# Sheet2.net
KiCad netlist of a schematic drawn in Altium Designer
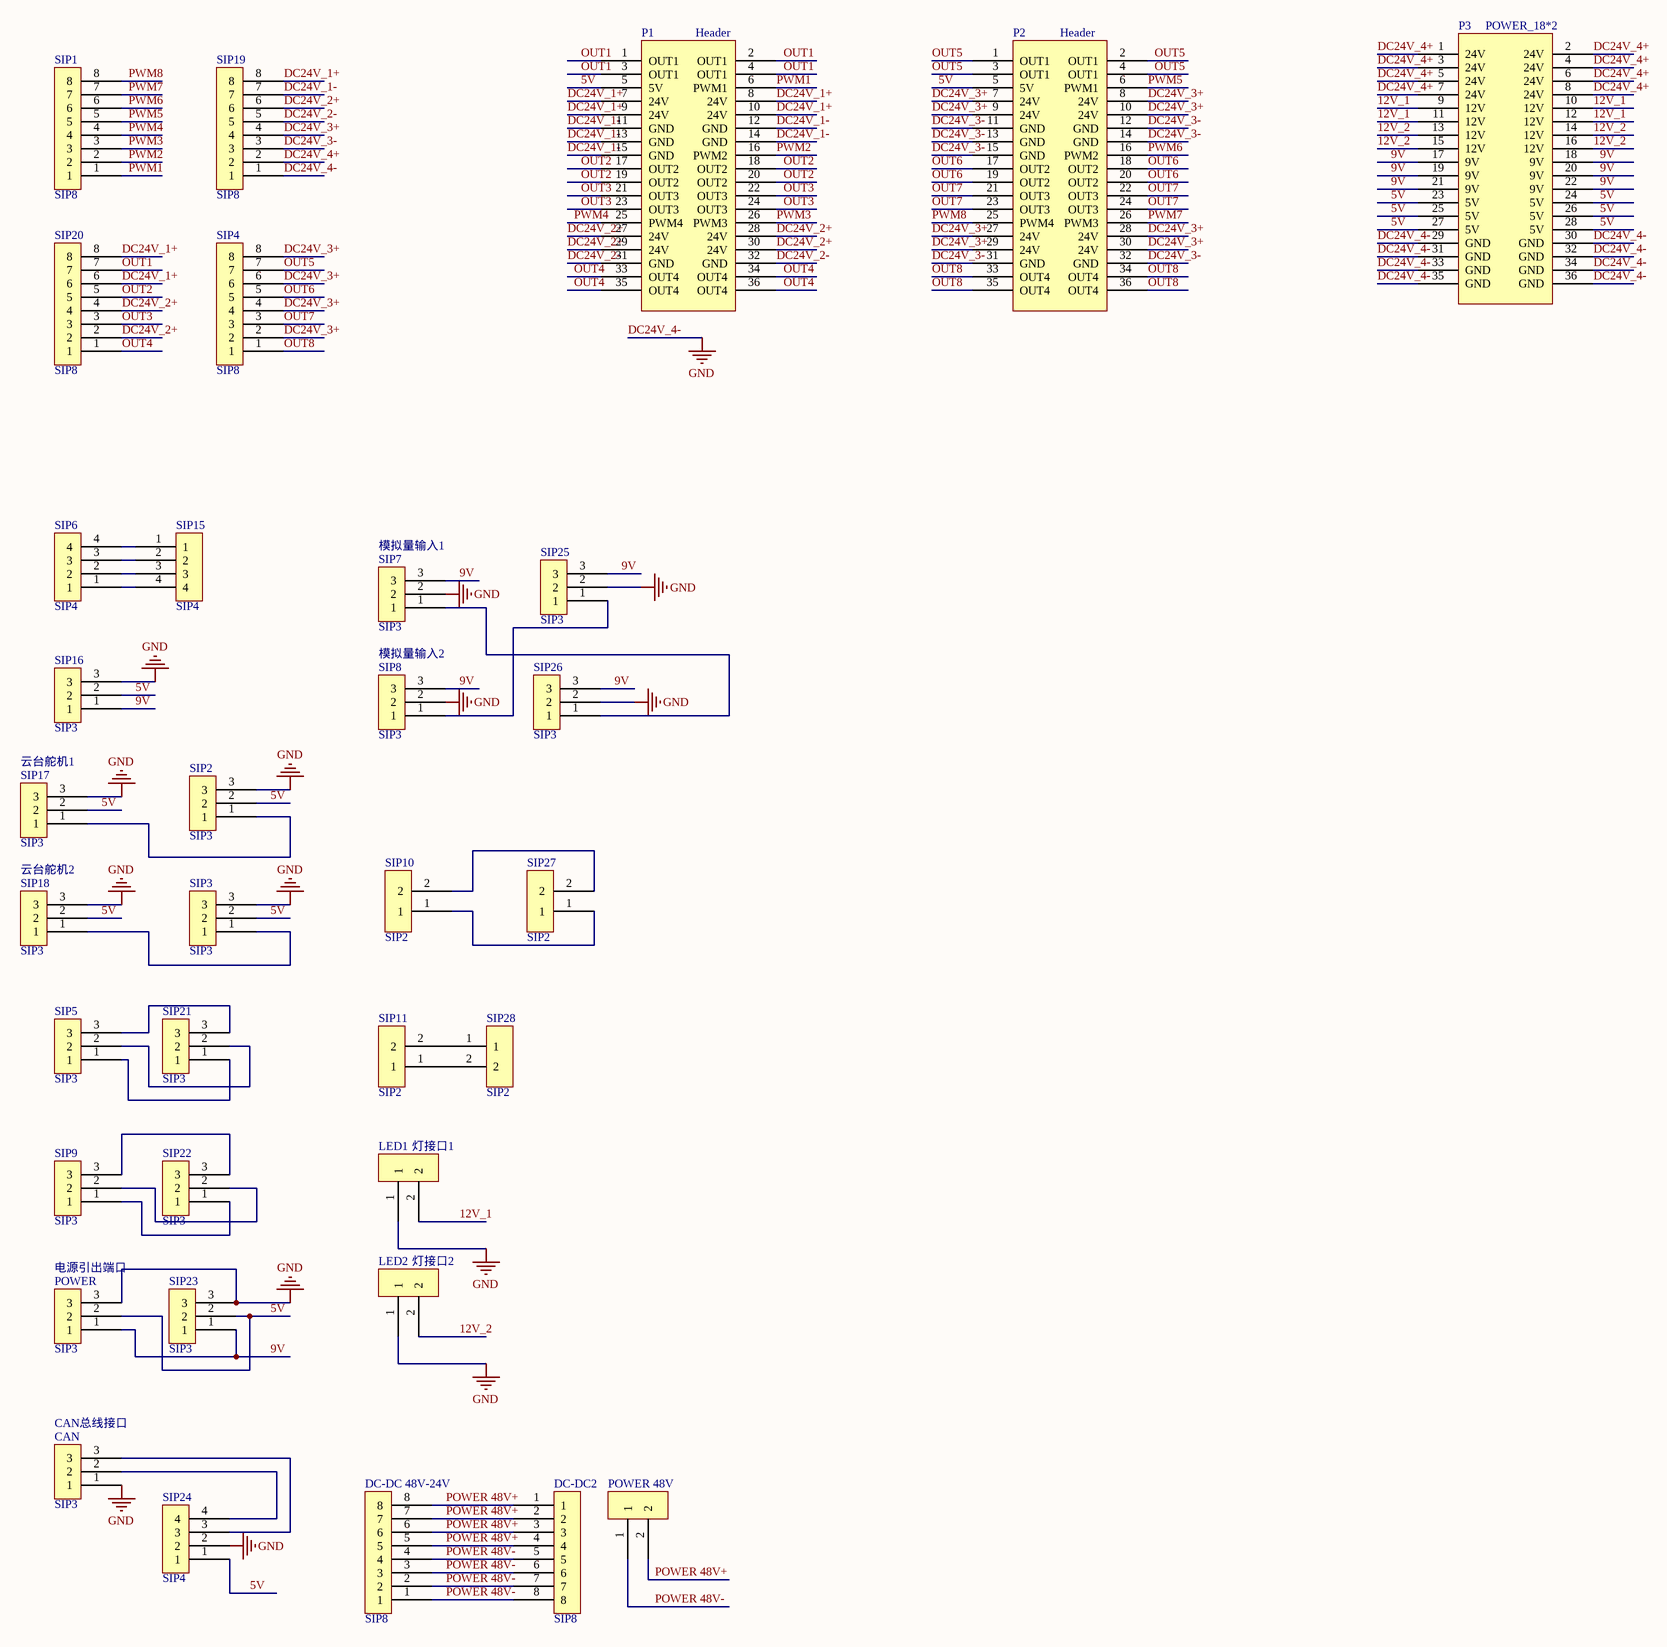
[diagram p0: Sheet2.SchDoc]

(export (version "E")
  (design (tool "Eeschema 10.0.6"))
  (components
    (comp (ref "CAN") (value "SIP3") (footprint "SIP3") (libsource (lib "qudong") (part "SIP3")))
    (comp (ref "DC-DC 48V-24V")
      (value "SIP8")
      (footprint "DIP8-3MM")
      (libsource (lib "qudong") (part "SIP8"))
    )
    (comp (ref "DC-DC2") (value "SIP8") (footprint "DIP8-3MM") (libsource (lib "") (part "SIP8_1")))
    (comp (ref "LED1") (value "SIP2") (footprint "SIP2-3MM") (libsource (lib "qudong") (part "SIP2")))
    (comp (ref "LED2") (value "SIP2") (footprint "SIP2-3MM") (libsource (lib "qudong") (part "SIP2")))
    (comp (ref "P1") (value "Header") (footprint "DIP36-3.96MM") (libsource (lib "qudong") (part "Header")))
    (comp (ref "P2") (value "Header") (footprint "DIP36-3.96MM") (libsource (lib "qudong") (part "Header")))
    (comp (ref "P3")
      (value "POWER_18*2")
      (footprint "DIP36-3.96MM")
      (libsource (lib "qudong") (part "POWER_18*2"))
    )
    (comp (ref "POWER") (value "SIP3") (footprint "SIP3") (libsource (lib "qudong") (part "SIP3")))
    (comp (ref "POWER 48V") (value "SIP2") (footprint "SIP2-3MM") (libsource (lib "qudong") (part "SIP2")))
    (comp (ref "SIP1") (value "SIP8") (footprint "SIP8") (libsource (lib "qudong") (part "SIP8")))
    (comp (ref "SIP2") (value "SIP3") (footprint "SIP3") (libsource (lib "qudong") (part "SIP3")))
    (comp (ref "SIP3") (value "SIP3") (footprint "SIP3") (libsource (lib "qudong") (part "SIP3")))
    (comp (ref "SIP4") (value "SIP8") (footprint "DIP8-3MM") (libsource (lib "qudong") (part "SIP8")))
    (comp (ref "SIP5") (value "SIP3") (footprint "SIP3") (libsource (lib "qudong") (part "SIP3")))
    (comp (ref "SIP6") (value "SIP4") (footprint "SIP4") (libsource (lib "qudong") (part "SIP4")))
    (comp (ref "SIP7") (value "SIP3") (footprint "SIP3") (libsource (lib "qudong") (part "SIP3")))
    (comp (ref "SIP8") (value "SIP3") (footprint "SIP3") (libsource (lib "qudong") (part "SIP3")))
    (comp (ref "SIP9") (value "SIP3") (footprint "SIP3") (libsource (lib "qudong") (part "SIP3")))
    (comp (ref "SIP10") (value "SIP2") (footprint "SIP2") (libsource (lib "") (part "SIP2_1")))
    (comp (ref "SIP11") (value "SIP2") (footprint "SIP2") (libsource (lib "") (part "SIP2_1")))
    (comp (ref "SIP15") (value "SIP4") (footprint "SIP4") (libsource (lib "") (part "SIP4_1")))
    (comp (ref "SIP16") (value "SIP3") (footprint "SIP3") (libsource (lib "qudong") (part "SIP3")))
    (comp (ref "SIP17") (value "SIP3") (footprint "SIP3") (libsource (lib "qudong") (part "SIP3")))
    (comp (ref "SIP18") (value "SIP3") (footprint "SIP3") (libsource (lib "qudong") (part "SIP3")))
    (comp (ref "SIP19") (value "SIP8") (footprint "DIP8-3MM") (libsource (lib "qudong") (part "SIP8")))
    (comp (ref "SIP20") (value "SIP8") (footprint "DIP8-3MM") (libsource (lib "qudong") (part "SIP8")))
    (comp (ref "SIP21") (value "SIP3") (footprint "SIP3") (libsource (lib "qudong") (part "SIP3")))
    (comp (ref "SIP22") (value "SIP3") (footprint "SIP3") (libsource (lib "qudong") (part "SIP3")))
    (comp (ref "SIP23") (value "SIP3") (footprint "SIP3") (libsource (lib "qudong") (part "SIP3")))
    (comp (ref "SIP24") (value "SIP4") (footprint "SIP4") (libsource (lib "qudong") (part "SIP4")))
    (comp (ref "SIP25") (value "SIP3") (footprint "SIP3") (libsource (lib "qudong") (part "SIP3")))
    (comp (ref "SIP26") (value "SIP3") (footprint "SIP3") (libsource (lib "qudong") (part "SIP3")))
    (comp (ref "SIP27") (value "SIP2") (footprint "SIP2") (libsource (lib "") (part "SIP2_1")))
    (comp (ref "SIP28") (value "SIP2") (footprint "SIP2") (libsource (lib "") (part "SIP2_2")))
  )
  (nets
    (net (code "1") (name "/5V") (class "Default")
      (node (ref "P1") (pin "5") (pinfunction "5V_5") (pintype "passive"))
      (node (ref "P2") (pin "5") (pinfunction "5V_5") (pintype "passive"))
      (node (ref "P3") (pin "23") (pinfunction "5V_23") (pintype "passive"))
      (node (ref "P3") (pin "24") (pinfunction "5V_24") (pintype "passive"))
      (node (ref "P3") (pin "25") (pinfunction "5V_25") (pintype "passive"))
      (node (ref "P3") (pin "26") (pinfunction "5V_26") (pintype "passive"))
      (node (ref "P3") (pin "27") (pinfunction "5V_27") (pintype "passive"))
      (node (ref "P3") (pin "28") (pinfunction "5V_28") (pintype "passive"))
      (node (ref "POWER") (pin "2") (pinfunction "2_2") (pintype "passive"))
      (node (ref "SIP16") (pin "2") (pinfunction "2_2") (pintype "passive"))
      (node (ref "SIP17") (pin "2") (pinfunction "2_2") (pintype "passive"))
      (node (ref "SIP18") (pin "2") (pinfunction "2_2") (pintype "passive"))
      (node (ref "SIP2") (pin "2") (pinfunction "2_2") (pintype "passive"))
      (node (ref "SIP23") (pin "2") (pinfunction "2_2") (pintype "passive"))
      (node (ref "SIP24") (pin "1") (pinfunction "1_1") (pintype "passive"))
      (node (ref "SIP3") (pin "2") (pinfunction "2_2") (pintype "passive"))
    )
    (net (code "2") (name "/9V") (class "Default")
      (node (ref "P3") (pin "17") (pinfunction "9V_17") (pintype "passive"))
      (node (ref "P3") (pin "18") (pinfunction "9V_18") (pintype "passive"))
      (node (ref "P3") (pin "19") (pinfunction "9V_19") (pintype "passive"))
      (node (ref "P3") (pin "20") (pinfunction "9V_20") (pintype "passive"))
      (node (ref "P3") (pin "21") (pinfunction "9V_21") (pintype "passive"))
      (node (ref "P3") (pin "22") (pinfunction "9V_22") (pintype "passive"))
      (node (ref "POWER") (pin "1") (pinfunction "1_1") (pintype "passive"))
      (node (ref "SIP16") (pin "1") (pinfunction "1_1") (pintype "passive"))
      (node (ref "SIP23") (pin "1") (pinfunction "1_1") (pintype "passive"))
      (node (ref "SIP25") (pin "3") (pinfunction "3_3") (pintype "passive"))
      (node (ref "SIP26") (pin "3") (pinfunction "3_3") (pintype "passive"))
      (node (ref "SIP7") (pin "3") (pinfunction "3_3") (pintype "passive"))
      (node (ref "SIP8") (pin "3") (pinfunction "3_3") (pintype "passive"))
    )
    (net (code "3") (name "/12V_1") (class "Default")
      (node (ref "LED1") (pin "2") (pinfunction "2_2") (pintype "passive"))
      (node (ref "P3") (pin "10") (pinfunction "12V_10") (pintype "passive"))
      (node (ref "P3") (pin "11") (pinfunction "12V_11") (pintype "passive"))
      (node (ref "P3") (pin "12") (pinfunction "12V_12") (pintype "passive"))
      (node (ref "P3") (pin "9") (pinfunction "12V_9") (pintype "passive"))
    )
    (net (code "4") (name "/12V_2") (class "Default")
      (node (ref "LED2") (pin "2") (pinfunction "2_2") (pintype "passive"))
      (node (ref "P3") (pin "13") (pinfunction "12V_13") (pintype "passive"))
      (node (ref "P3") (pin "14") (pinfunction "12V_14") (pintype "passive"))
      (node (ref "P3") (pin "15") (pinfunction "12V_15") (pintype "passive"))
      (node (ref "P3") (pin "16") (pinfunction "12V_16") (pintype "passive"))
    )
    (net (code "5") (name "/DC24V_1+") (class "Default")
      (node (ref "P1") (pin "10") (pinfunction "24V_10") (pintype "passive"))
      (node (ref "P1") (pin "7") (pinfunction "24V_7") (pintype "passive"))
      (node (ref "P1") (pin "8") (pinfunction "24V_8") (pintype "passive"))
      (node (ref "P1") (pin "9") (pinfunction "24V_9") (pintype "passive"))
      (node (ref "SIP19") (pin "8") (pinfunction "8_8") (pintype "passive"))
      (node (ref "SIP20") (pin "6") (pinfunction "6_6") (pintype "passive"))
      (node (ref "SIP20") (pin "8") (pinfunction "8_8") (pintype "passive"))
    )
    (net (code "6") (name "/DC24V_1-") (class "Default")
      (node (ref "P1") (pin "11") (pinfunction "GND_11") (pintype "passive"))
      (node (ref "P1") (pin "12") (pinfunction "GND_12") (pintype "passive"))
      (node (ref "P1") (pin "13") (pinfunction "GND_13") (pintype "passive"))
      (node (ref "P1") (pin "14") (pinfunction "GND_14") (pintype "passive"))
      (node (ref "P1") (pin "15") (pinfunction "GND_15") (pintype "passive"))
      (node (ref "SIP19") (pin "7") (pinfunction "7_7") (pintype "passive"))
    )
    (net (code "7") (name "/DC24V_2+") (class "Default")
      (node (ref "P1") (pin "27") (pinfunction "24V_27") (pintype "passive"))
      (node (ref "P1") (pin "28") (pinfunction "24V_28") (pintype "passive"))
      (node (ref "P1") (pin "29") (pinfunction "24V_29") (pintype "passive"))
      (node (ref "P1") (pin "30") (pinfunction "24V_30") (pintype "passive"))
      (node (ref "SIP19") (pin "6") (pinfunction "6_6") (pintype "passive"))
      (node (ref "SIP20") (pin "2") (pinfunction "2_2") (pintype "passive"))
      (node (ref "SIP20") (pin "4") (pinfunction "4_4") (pintype "passive"))
    )
    (net (code "8") (name "/DC24V_2-") (class "Default")
      (node (ref "P1") (pin "31") (pinfunction "GND_31") (pintype "passive"))
      (node (ref "P1") (pin "32") (pinfunction "GND_32") (pintype "passive"))
      (node (ref "SIP19") (pin "5") (pinfunction "5_5") (pintype "passive"))
    )
    (net (code "9") (name "/DC24V_3+") (class "Default")
      (node (ref "P2") (pin "10") (pinfunction "24V_10") (pintype "passive"))
      (node (ref "P2") (pin "27") (pinfunction "24V_27") (pintype "passive"))
      (node (ref "P2") (pin "28") (pinfunction "24V_28") (pintype "passive"))
      (node (ref "P2") (pin "29") (pinfunction "24V_29") (pintype "passive"))
      (node (ref "P2") (pin "30") (pinfunction "24V_30") (pintype "passive"))
      (node (ref "P2") (pin "7") (pinfunction "24V_7") (pintype "passive"))
      (node (ref "P2") (pin "8") (pinfunction "24V_8") (pintype "passive"))
      (node (ref "P2") (pin "9") (pinfunction "24V_9") (pintype "passive"))
      (node (ref "SIP19") (pin "4") (pinfunction "4_4") (pintype "passive"))
      (node (ref "SIP4") (pin "2") (pinfunction "2_2") (pintype "passive"))
      (node (ref "SIP4") (pin "4") (pinfunction "4_4") (pintype "passive"))
      (node (ref "SIP4") (pin "6") (pinfunction "6_6") (pintype "passive"))
      (node (ref "SIP4") (pin "8") (pinfunction "8_8") (pintype "passive"))
    )
    (net (code "10") (name "/DC24V_3-") (class "Default")
      (node (ref "P2") (pin "11") (pinfunction "GND_11") (pintype "passive"))
      (node (ref "P2") (pin "12") (pinfunction "GND_12") (pintype "passive"))
      (node (ref "P2") (pin "13") (pinfunction "GND_13") (pintype "passive"))
      (node (ref "P2") (pin "14") (pinfunction "GND_14") (pintype "passive"))
      (node (ref "P2") (pin "15") (pinfunction "GND_15") (pintype "passive"))
      (node (ref "P2") (pin "31") (pinfunction "GND_31") (pintype "passive"))
      (node (ref "P2") (pin "32") (pinfunction "GND_32") (pintype "passive"))
      (node (ref "SIP19") (pin "3") (pinfunction "3_3") (pintype "passive"))
    )
    (net (code "11") (name "/DC24V_4+") (class "Default")
      (node (ref "P3") (pin "1") (pinfunction "24V_1") (pintype "passive"))
      (node (ref "P3") (pin "2") (pinfunction "24V_2") (pintype "passive"))
      (node (ref "P3") (pin "3") (pinfunction "24V_3") (pintype "passive"))
      (node (ref "P3") (pin "4") (pinfunction "24V_4") (pintype "passive"))
      (node (ref "P3") (pin "5") (pinfunction "24V_5") (pintype "passive"))
      (node (ref "P3") (pin "6") (pinfunction "24V_6") (pintype "passive"))
      (node (ref "P3") (pin "7") (pinfunction "24V_7") (pintype "passive"))
      (node (ref "P3") (pin "8") (pinfunction "24V_8") (pintype "passive"))
      (node (ref "SIP19") (pin "2") (pinfunction "2_2") (pintype "passive"))
    )
    (net (code "12") (name "/OUT1") (class "Default")
      (node (ref "P1") (pin "1") (pinfunction "OUT1_1") (pintype "passive"))
      (node (ref "P1") (pin "2") (pinfunction "OUT1_2") (pintype "passive"))
      (node (ref "P1") (pin "3") (pinfunction "OUT1_3") (pintype "passive"))
      (node (ref "P1") (pin "4") (pinfunction "OUT1_4") (pintype "passive"))
      (node (ref "SIP20") (pin "7") (pinfunction "7_7") (pintype "passive"))
    )
    (net (code "13") (name "/OUT2") (class "Default")
      (node (ref "P1") (pin "17") (pinfunction "OUT2_17") (pintype "passive"))
      (node (ref "P1") (pin "18") (pinfunction "OUT2_18") (pintype "passive"))
      (node (ref "P1") (pin "19") (pinfunction "OUT2_19") (pintype "passive"))
      (node (ref "P1") (pin "20") (pinfunction "OUT2_20") (pintype "passive"))
      (node (ref "SIP20") (pin "5") (pinfunction "5_5") (pintype "passive"))
    )
    (net (code "14") (name "/OUT3") (class "Default")
      (node (ref "P1") (pin "21") (pinfunction "OUT3_21") (pintype "passive"))
      (node (ref "P1") (pin "22") (pinfunction "OUT3_22") (pintype "passive"))
      (node (ref "P1") (pin "23") (pinfunction "OUT3_23") (pintype "passive"))
      (node (ref "P1") (pin "24") (pinfunction "OUT3_24") (pintype "passive"))
      (node (ref "SIP20") (pin "3") (pinfunction "3_3") (pintype "passive"))
    )
    (net (code "15") (name "/OUT4") (class "Default")
      (node (ref "P1") (pin "33") (pinfunction "OUT4_33") (pintype "passive"))
      (node (ref "P1") (pin "34") (pinfunction "OUT4_34") (pintype "passive"))
      (node (ref "P1") (pin "35") (pinfunction "OUT4_35") (pintype "passive"))
      (node (ref "P1") (pin "36") (pinfunction "OUT4_36") (pintype "passive"))
      (node (ref "SIP20") (pin "1") (pinfunction "1_1") (pintype "passive"))
    )
    (net (code "16") (name "/OUT5") (class "Default")
      (node (ref "P2") (pin "1") (pinfunction "OUT1_1") (pintype "passive"))
      (node (ref "P2") (pin "2") (pinfunction "OUT1_2") (pintype "passive"))
      (node (ref "P2") (pin "3") (pinfunction "OUT1_3") (pintype "passive"))
      (node (ref "P2") (pin "4") (pinfunction "OUT1_4") (pintype "passive"))
      (node (ref "SIP4") (pin "7") (pinfunction "7_7") (pintype "passive"))
    )
    (net (code "17") (name "/OUT6") (class "Default")
      (node (ref "P2") (pin "17") (pinfunction "OUT2_17") (pintype "passive"))
      (node (ref "P2") (pin "18") (pinfunction "OUT2_18") (pintype "passive"))
      (node (ref "P2") (pin "19") (pinfunction "OUT2_19") (pintype "passive"))
      (node (ref "P2") (pin "20") (pinfunction "OUT2_20") (pintype "passive"))
      (node (ref "SIP4") (pin "5") (pinfunction "5_5") (pintype "passive"))
    )
    (net (code "18") (name "/OUT7") (class "Default")
      (node (ref "P2") (pin "21") (pinfunction "OUT3_21") (pintype "passive"))
      (node (ref "P2") (pin "22") (pinfunction "OUT3_22") (pintype "passive"))
      (node (ref "P2") (pin "23") (pinfunction "OUT3_23") (pintype "passive"))
      (node (ref "P2") (pin "24") (pinfunction "OUT3_24") (pintype "passive"))
      (node (ref "SIP4") (pin "3") (pinfunction "3_3") (pintype "passive"))
    )
    (net (code "19") (name "/OUT8") (class "Default")
      (node (ref "P2") (pin "33") (pinfunction "OUT4_33") (pintype "passive"))
      (node (ref "P2") (pin "34") (pinfunction "OUT4_34") (pintype "passive"))
      (node (ref "P2") (pin "35") (pinfunction "OUT4_35") (pintype "passive"))
      (node (ref "P2") (pin "36") (pinfunction "OUT4_36") (pintype "passive"))
      (node (ref "SIP4") (pin "1") (pinfunction "1_1") (pintype "passive"))
    )
    (net (code "20") (name "/POWER 48V+") (class "Default")
      (node (ref "DC-DC 48V-24V") (pin "5") (pinfunction "5_5") (pintype "passive"))
      (node (ref "DC-DC 48V-24V") (pin "6") (pinfunction "6_6") (pintype "passive"))
      (node (ref "DC-DC 48V-24V") (pin "7") (pinfunction "7_7") (pintype "passive"))
      (node (ref "DC-DC 48V-24V") (pin "8") (pinfunction "8_8") (pintype "passive"))
      (node (ref "DC-DC2") (pin "1") (pinfunction "1_1") (pintype "passive"))
      (node (ref "DC-DC2") (pin "2") (pinfunction "2_2") (pintype "passive"))
      (node (ref "DC-DC2") (pin "3") (pinfunction "3_3") (pintype "passive"))
      (node (ref "DC-DC2") (pin "4") (pinfunction "4_4") (pintype "passive"))
      (node (ref "POWER 48V") (pin "2") (pinfunction "2_2") (pintype "passive"))
    )
    (net (code "21") (name "/POWER 48V-") (class "Default")
      (node (ref "DC-DC 48V-24V") (pin "1") (pinfunction "1_1") (pintype "passive"))
      (node (ref "DC-DC 48V-24V") (pin "2") (pinfunction "2_2") (pintype "passive"))
      (node (ref "DC-DC 48V-24V") (pin "3") (pinfunction "3_3") (pintype "passive"))
      (node (ref "DC-DC 48V-24V") (pin "4") (pinfunction "4_4") (pintype "passive"))
      (node (ref "DC-DC2") (pin "5") (pinfunction "5_5") (pintype "passive"))
      (node (ref "DC-DC2") (pin "6") (pinfunction "6_6") (pintype "passive"))
      (node (ref "DC-DC2") (pin "7") (pinfunction "7_7") (pintype "passive"))
      (node (ref "DC-DC2") (pin "8") (pinfunction "8_8") (pintype "passive"))
      (node (ref "POWER 48V") (pin "1") (pinfunction "1_1") (pintype "passive"))
    )
    (net (code "22") (name "/PWM1") (class "Default")
      (node (ref "P1") (pin "6") (pinfunction "PWM1_6") (pintype "passive"))
      (node (ref "SIP1") (pin "1") (pinfunction "1_1") (pintype "passive"))
    )
    (net (code "23") (name "/PWM2") (class "Default")
      (node (ref "P1") (pin "16") (pinfunction "PWM2_16") (pintype "passive"))
      (node (ref "SIP1") (pin "2") (pinfunction "2_2") (pintype "passive"))
    )
    (net (code "24") (name "/PWM3") (class "Default")
      (node (ref "P1") (pin "26") (pinfunction "PWM3_26") (pintype "passive"))
      (node (ref "SIP1") (pin "3") (pinfunction "3_3") (pintype "passive"))
    )
    (net (code "25") (name "/PWM4") (class "Default")
      (node (ref "P1") (pin "25") (pinfunction "PWM4_25") (pintype "passive"))
      (node (ref "SIP1") (pin "4") (pinfunction "4_4") (pintype "passive"))
    )
    (net (code "26") (name "/PWM5") (class "Default")
      (node (ref "P2") (pin "6") (pinfunction "PWM1_6") (pintype "passive"))
      (node (ref "SIP1") (pin "5") (pinfunction "5_5") (pintype "passive"))
    )
    (net (code "27") (name "/PWM6") (class "Default")
      (node (ref "P2") (pin "16") (pinfunction "PWM2_16") (pintype "passive"))
      (node (ref "SIP1") (pin "6") (pinfunction "6_6") (pintype "passive"))
    )
    (net (code "28") (name "/PWM7") (class "Default")
      (node (ref "P2") (pin "26") (pinfunction "PWM3_26") (pintype "passive"))
      (node (ref "SIP1") (pin "7") (pinfunction "7_7") (pintype "passive"))
    )
    (net (code "29") (name "/PWM8") (class "Default")
      (node (ref "P2") (pin "25") (pinfunction "PWM4_25") (pintype "passive"))
      (node (ref "SIP1") (pin "8") (pinfunction "8_8") (pintype "passive"))
    )
    (net (code "30") (name "GND") (class "Default")
      (node (ref "CAN") (pin "1") (pinfunction "1_1") (pintype "passive"))
      (node (ref "LED1") (pin "1") (pinfunction "1_1") (pintype "passive"))
      (node (ref "LED2") (pin "1") (pinfunction "1_1") (pintype "passive"))
      (node (ref "P3") (pin "29") (pinfunction "GND_29") (pintype "passive"))
      (node (ref "P3") (pin "30") (pinfunction "GND_30") (pintype "passive"))
      (node (ref "P3") (pin "31") (pinfunction "GND_31") (pintype "passive"))
      (node (ref "P3") (pin "32") (pinfunction "GND_32") (pintype "passive"))
      (node (ref "P3") (pin "33") (pinfunction "GND_33") (pintype "passive"))
      (node (ref "P3") (pin "34") (pinfunction "GND_34") (pintype "passive"))
      (node (ref "P3") (pin "35") (pinfunction "GND_35") (pintype "passive"))
      (node (ref "P3") (pin "36") (pinfunction "GND_36") (pintype "passive"))
      (node (ref "POWER") (pin "3") (pinfunction "3_3") (pintype "passive"))
      (node (ref "SIP16") (pin "3") (pinfunction "3_3") (pintype "passive"))
      (node (ref "SIP17") (pin "3") (pinfunction "3_3") (pintype "passive"))
      (node (ref "SIP18") (pin "3") (pinfunction "3_3") (pintype "passive"))
      (node (ref "SIP19") (pin "1") (pinfunction "1_1") (pintype "passive"))
      (node (ref "SIP2") (pin "3") (pinfunction "3_3") (pintype "passive"))
      (node (ref "SIP23") (pin "3") (pinfunction "3_3") (pintype "passive"))
      (node (ref "SIP24") (pin "2") (pinfunction "2_2") (pintype "passive"))
      (node (ref "SIP25") (pin "2") (pinfunction "2_2") (pintype "passive"))
      (node (ref "SIP26") (pin "2") (pinfunction "2_2") (pintype "passive"))
      (node (ref "SIP3") (pin "3") (pinfunction "3_3") (pintype "passive"))
      (node (ref "SIP7") (pin "2") (pinfunction "2_2") (pintype "passive"))
      (node (ref "SIP8") (pin "2") (pinfunction "2_2") (pintype "passive"))
    )
    (net (code "31") (name "Net-(CAN-Pad2)") (class "Default")
      (node (ref "CAN") (pin "2") (pinfunction "2_2") (pintype "passive"))
      (node (ref "SIP24") (pin "4") (pinfunction "4_4") (pintype "passive"))
    )
    (net (code "32") (name "Net-(CAN-Pad3)") (class "Default")
      (node (ref "CAN") (pin "3") (pinfunction "3_3") (pintype "passive"))
      (node (ref "SIP24") (pin "3") (pinfunction "3_3") (pintype "passive"))
    )
    (net (code "33") (name "Net-(SIP10-Pad1)") (class "Default")
      (node (ref "SIP10") (pin "1") (pinfunction "1_1") (pintype "passive"))
      (node (ref "SIP27") (pin "1") (pinfunction "1_1") (pintype "passive"))
    )
    (net (code "34") (name "Net-(SIP10-Pad2)") (class "Default")
      (node (ref "SIP10") (pin "2") (pinfunction "2_2") (pintype "passive"))
      (node (ref "SIP27") (pin "2") (pinfunction "2_2") (pintype "passive"))
    )
    (net (code "35") (name "Net-(SIP11-Pad1)") (class "Default")
      (node (ref "SIP11") (pin "1") (pinfunction "1_1") (pintype "passive"))
      (node (ref "SIP28") (pin "2") (pinfunction "2_2") (pintype "passive"))
    )
    (net (code "36") (name "Net-(SIP11-Pad2)") (class "Default")
      (node (ref "SIP11") (pin "2") (pinfunction "2_2") (pintype "passive"))
      (node (ref "SIP28") (pin "1") (pinfunction "1_1") (pintype "passive"))
    )
    (net (code "37") (name "Net-(SIP15-Pad1)") (class "Default")
      (node (ref "SIP15") (pin "1") (pinfunction "1_1") (pintype "passive"))
      (node (ref "SIP6") (pin "4") (pinfunction "4_4") (pintype "passive"))
    )
    (net (code "38") (name "Net-(SIP15-Pad2)") (class "Default")
      (node (ref "SIP15") (pin "2") (pinfunction "2_2") (pintype "passive"))
      (node (ref "SIP6") (pin "3") (pinfunction "3_3") (pintype "passive"))
    )
    (net (code "39") (name "Net-(SIP15-Pad3)") (class "Default")
      (node (ref "SIP15") (pin "3") (pinfunction "3_3") (pintype "passive"))
      (node (ref "SIP6") (pin "2") (pinfunction "2_2") (pintype "passive"))
    )
    (net (code "40") (name "Net-(SIP15-Pad4)") (class "Default")
      (node (ref "SIP15") (pin "4") (pinfunction "4_4") (pintype "passive"))
      (node (ref "SIP6") (pin "1") (pinfunction "1_1") (pintype "passive"))
    )
    (net (code "41") (name "Net-(SIP17-Pad1)") (class "Default")
      (node (ref "SIP17") (pin "1") (pinfunction "1_1") (pintype "passive"))
      (node (ref "SIP2") (pin "1") (pinfunction "1_1") (pintype "passive"))
    )
    (net (code "42") (name "Net-(SIP18-Pad1)") (class "Default")
      (node (ref "SIP18") (pin "1") (pinfunction "1_1") (pintype "passive"))
      (node (ref "SIP3") (pin "1") (pinfunction "1_1") (pintype "passive"))
    )
    (net (code "43") (name "Net-(SIP21-Pad1)") (class "Default")
      (node (ref "SIP21") (pin "1") (pinfunction "1_1") (pintype "passive"))
      (node (ref "SIP5") (pin "1") (pinfunction "1_1") (pintype "passive"))
    )
    (net (code "44") (name "Net-(SIP21-Pad2)") (class "Default")
      (node (ref "SIP21") (pin "2") (pinfunction "2_2") (pintype "passive"))
      (node (ref "SIP5") (pin "2") (pinfunction "2_2") (pintype "passive"))
    )
    (net (code "45") (name "Net-(SIP21-Pad3)") (class "Default")
      (node (ref "SIP21") (pin "3") (pinfunction "3_3") (pintype "passive"))
      (node (ref "SIP5") (pin "3") (pinfunction "3_3") (pintype "passive"))
    )
    (net (code "46") (name "Net-(SIP22-Pad1)") (class "Default")
      (node (ref "SIP22") (pin "1") (pinfunction "1_1") (pintype "passive"))
      (node (ref "SIP9") (pin "1") (pinfunction "1_1") (pintype "passive"))
    )
    (net (code "47") (name "Net-(SIP22-Pad2)") (class "Default")
      (node (ref "SIP22") (pin "2") (pinfunction "2_2") (pintype "passive"))
      (node (ref "SIP9") (pin "2") (pinfunction "2_2") (pintype "passive"))
    )
    (net (code "48") (name "Net-(SIP22-Pad3)") (class "Default")
      (node (ref "SIP22") (pin "3") (pinfunction "3_3") (pintype "passive"))
      (node (ref "SIP9") (pin "3") (pinfunction "3_3") (pintype "passive"))
    )
    (net (code "49") (name "Net-(SIP25-Pad1)") (class "Default")
      (node (ref "SIP25") (pin "1") (pinfunction "1_1") (pintype "passive"))
      (node (ref "SIP8") (pin "1") (pinfunction "1_1") (pintype "passive"))
    )
    (net (code "50") (name "Net-(SIP26-Pad1)") (class "Default")
      (node (ref "SIP26") (pin "1") (pinfunction "1_1") (pintype "passive"))
      (node (ref "SIP7") (pin "1") (pinfunction "1_1") (pintype "passive"))
    )
  )
)
